# MEZ_ALL_IND.net
KiCad netlist of a schematic drawn in Altium Designer
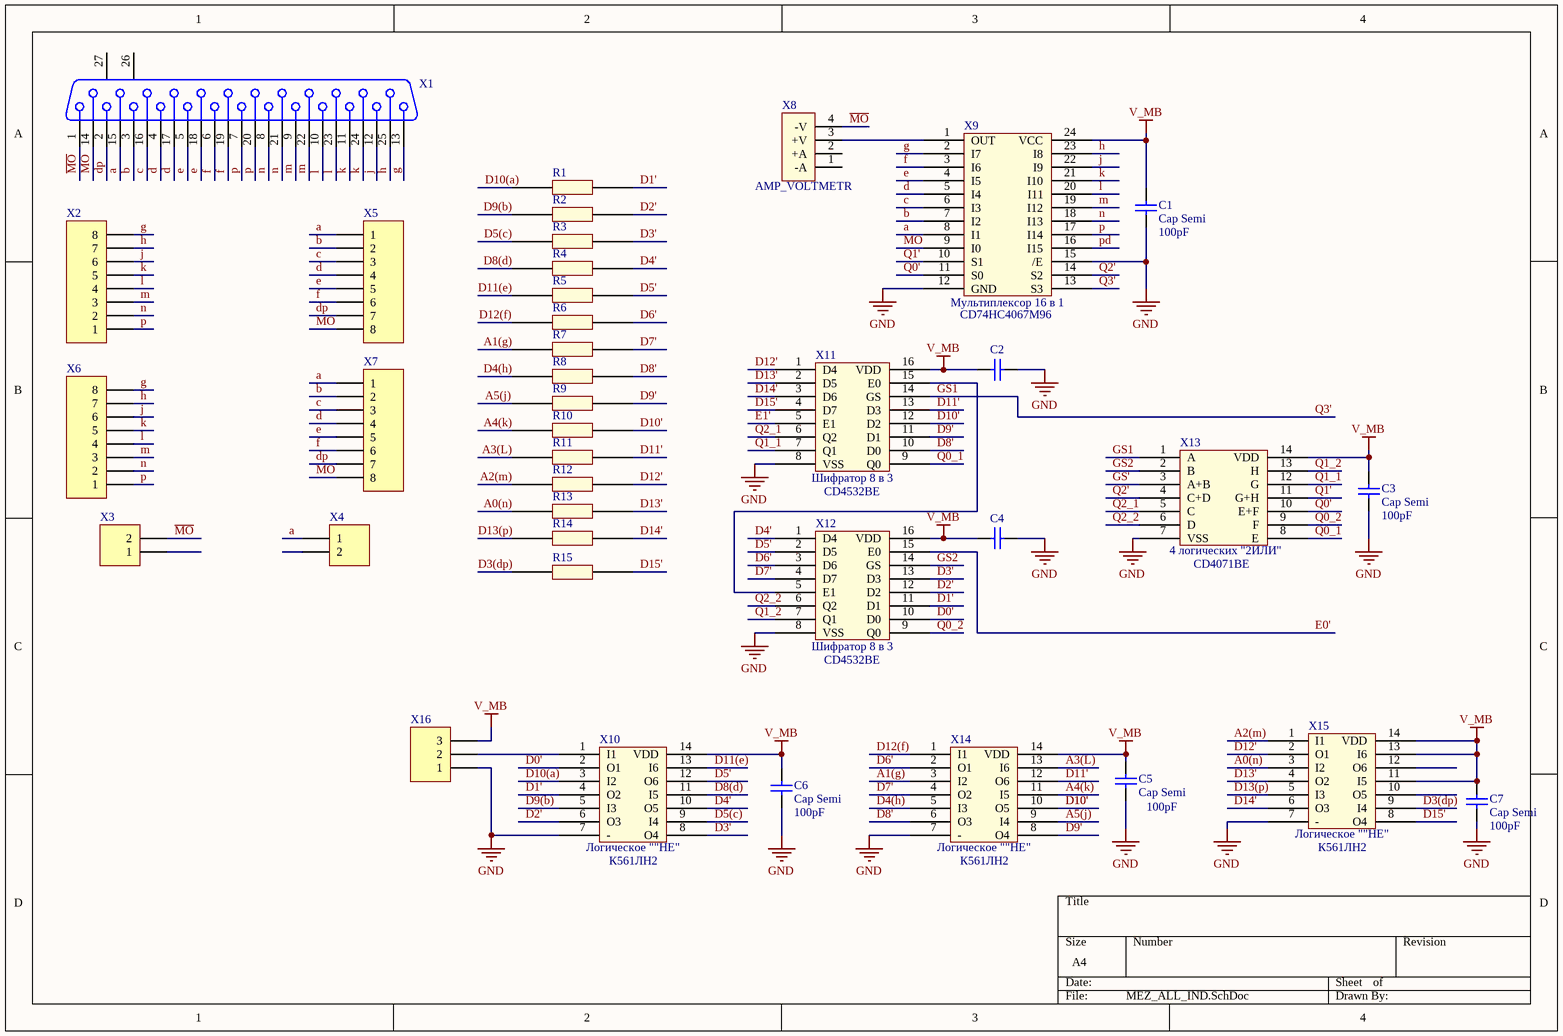
[diagram p0: MEZ_ALL_IND.SchDoc]

(export (version "E")
  (design (tool "Eeschema 10.0.6"))
  (components
    (comp (ref "C1")
      (value "Cap Semi")
      (footprint "C1206")
      (description "Capacitor (Semiconductor SIM Model)")
      (fields (field (name "ALTIUM_VALUE") "100pF") (field (name "PUBLISHER") "Altium Limited"))
      (libsource (lib "Miscellaneous Devices") (part "Cap Semi"))
    )
    (comp (ref "C2")
      (value "Cap Semi")
      (footprint "C1206")
      (description "Capacitor (Semiconductor SIM Model)")
      (fields (field (name "PUBLISHER") "Altium Limited"))
      (libsource (lib "Miscellaneous Devices") (part "Cap Semi"))
    )
    (comp (ref "C3")
      (value "Cap Semi")
      (footprint "C1206")
      (description "Capacitor (Semiconductor SIM Model)")
      (fields (field (name "ALTIUM_VALUE") "100pF") (field (name "PUBLISHER") "Altium Limited"))
      (libsource (lib "Miscellaneous Devices") (part "Cap Semi"))
    )
    (comp (ref "C4")
      (value "Cap Semi")
      (footprint "C1206")
      (description "Capacitor (Semiconductor SIM Model)")
      (fields (field (name "PUBLISHER") "Altium Limited"))
      (libsource (lib "Miscellaneous Devices") (part "Cap Semi"))
    )
    (comp (ref "C5")
      (value "Cap Semi")
      (footprint "C1206")
      (description "Capacitor (Semiconductor SIM Model)")
      (fields (field (name "ALTIUM_VALUE") "100pF") (field (name "PUBLISHER") "Altium Limited"))
      (libsource (lib "Miscellaneous Devices") (part "Cap Semi"))
    )
    (comp (ref "C6")
      (value "Cap Semi")
      (footprint "C1206")
      (description "Capacitor (Semiconductor SIM Model)")
      (fields (field (name "ALTIUM_VALUE") "100pF") (field (name "PUBLISHER") "Altium Limited"))
      (libsource (lib "Miscellaneous Devices") (part "Cap Semi"))
    )
    (comp (ref "C7")
      (value "Cap Semi")
      (footprint "C1206")
      (description "Capacitor (Semiconductor SIM Model)")
      (fields (field (name "ALTIUM_VALUE") "100pF") (field (name "PUBLISHER") "Altium Limited"))
      (libsource (lib "Miscellaneous Devices") (part "Cap Semi"))
    )
    (comp (ref "R1") (value "resistor") (footprint "RES 1608?") (libsource (lib "msp_SchLib") (part "RES")))
    (comp (ref "R2") (value "resistor") (footprint "RES 1608?") (libsource (lib "msp_SchLib") (part "RES")))
    (comp (ref "R3") (value "resistor") (footprint "RES 1608?") (libsource (lib "msp_SchLib") (part "RES")))
    (comp (ref "R4") (value "resistor") (footprint "RES 1608?") (libsource (lib "msp_SchLib") (part "RES")))
    (comp (ref "R5") (value "resistor") (footprint "RES 1608?") (libsource (lib "msp_SchLib") (part "RES")))
    (comp (ref "R6") (value "resistor") (footprint "RES 1608?") (libsource (lib "msp_SchLib") (part "RES")))
    (comp (ref "R7") (value "resistor") (footprint "RES 1608?") (libsource (lib "msp_SchLib") (part "RES")))
    (comp (ref "R8") (value "resistor") (footprint "RES 1608?") (libsource (lib "msp_SchLib") (part "RES")))
    (comp (ref "R9") (value "resistor") (footprint "RES 1608?") (libsource (lib "msp_SchLib") (part "RES")))
    (comp (ref "R10") (value "resistor") (footprint "RES 1608?") (libsource (lib "msp_SchLib") (part "RES")))
    (comp (ref "R11") (value "resistor") (footprint "RES 1608?") (libsource (lib "msp_SchLib") (part "RES")))
    (comp (ref "R12") (value "resistor") (footprint "RES 1608?") (libsource (lib "msp_SchLib") (part "RES")))
    (comp (ref "R13") (value "resistor") (footprint "RES 1608?") (libsource (lib "msp_SchLib") (part "RES")))
    (comp (ref "R14") (value "resistor") (footprint "RES 1608?") (libsource (lib "msp_SchLib") (part "RES")))
    (comp (ref "R15") (value "resistor") (footprint "RES 1608?") (libsource (lib "msp_SchLib") (part "RES")))
    (comp (ref "X1")
      (value "D Connector 25")
      (footprint "DSUB1.385-2H25A")
      (description "Receptacle Assembly, 25 Position, Right Angle")
      (fields (field (name "PUBLISHER") "Altium Limited"))
      (libsource (lib "Miscellaneous Connectors") (part "D Connector 25"))
    )
    (comp (ref "X2")
      (value "Header 8")
      (footprint "HDR1X8")
      (description "Header, 8-Pin")
      (fields (field (name "PUBLISHER") "Altium Limited"))
      (libsource (lib "Miscellaneous Connectors") (part "Header 8"))
    )
    (comp (ref "X3")
      (value "Header 2")
      (footprint "HDR1X2")
      (description "Header, 2-Pin")
      (fields (field (name "PUBLISHER") "Altium Limited"))
      (libsource (lib "Miscellaneous Connectors") (part "Header 2"))
    )
    (comp (ref "X4")
      (value "Header 2")
      (footprint "HDR1X2")
      (description "Header, 2-Pin")
      (fields (field (name "PUBLISHER") "Altium Limited"))
      (libsource (lib "") (part "Header 2_1"))
    )
    (comp (ref "X5")
      (value "Header 8")
      (footprint "HDR1X8")
      (description "Header, 8-Pin")
      (fields (field (name "PUBLISHER") "Altium Limited"))
      (libsource (lib "") (part "Header 8_1"))
    )
    (comp (ref "X6")
      (value "Header 8")
      (footprint "HDR1X8")
      (description "Header, 8-Pin")
      (fields (field (name "PUBLISHER") "Altium Limited"))
      (libsource (lib "Miscellaneous Connectors") (part "Header 8"))
    )
    (comp (ref "X7")
      (value "Header 8")
      (footprint "HDR1X8")
      (description "Header, 8-Pin")
      (fields (field (name "PUBLISHER") "Altium Limited"))
      (libsource (lib "") (part "Header 8_1"))
    )
    (comp (ref "X8")
      (value "AMP_VOLTMETR")
      (footprint "AMP_VOLTMETR")
      (libsource (lib "msp_SchLib") (part "AMP_VOLTMETR"))
    )
    (comp (ref "X9")
      (value "CD74HC4067M96")
      (footprint "SOIC-24")
      (description "16-и канальный аналоговый мультиплексор/ демультиплексор, [SO-24]")
      (libsource (lib "msp_SchLib") (part "CD74HC4067M96"))
    )
    (comp (ref "X10")
      (value "К561ЛН2")
      (description "Шесть логических элементов \"HЕ\" (DIP-14)")
      (libsource (lib "msp_SchLib") (part "К561ЛН2"))
    )
    (comp (ref "X11")
      (value "CD4532BE")
      (description "Шифратор приоритетный 8 - 3 [DIP-16]")
      (libsource (lib "msp_SchLib") (part "CD4532BE"))
    )
    (comp (ref "X12")
      (value "CD4532BE")
      (description "Шифратор приоритетный 8 - 3 [DIP-16]")
      (libsource (lib "msp_SchLib") (part "CD4532BE"))
    )
    (comp (ref "X13")
      (value "CD4071BE")
      (description "Четыре логических элемента \"2ИЛИ\", [DIP-14]")
      (libsource (lib "msp_SchLib") (part "CD4071BE"))
    )
    (comp (ref "X14")
      (value "К561ЛН2")
      (description "Шесть логических элементов \"HЕ\" (DIP-14)")
      (libsource (lib "msp_SchLib") (part "К561ЛН2"))
    )
    (comp (ref "X15")
      (value "К561ЛН2")
      (description "Шесть логических элементов \"HЕ\" (DIP-14)")
      (libsource (lib "msp_SchLib") (part "К561ЛН2"))
    )
    (comp (ref "X16")
      (value "Header 3")
      (footprint "HDR1X3")
      (description "Header, 3-Pin")
      (fields (field (name "PUBLISHER") "Altium Limited"))
      (libsource (lib "Miscellaneous Connectors") (part "Header 3"))
    )
  )
  (nets
    (net (code "1") (name "/A0(n)") (class "Default")
      (node (ref "R13") (pin "1") (pinfunction "1_1") (pintype "passive"))
      (node (ref "X15") (pin "3") (pinfunction "I2_3") (pintype "passive"))
    )
    (net (code "2") (name "/A1(g)") (class "Default")
      (node (ref "R7") (pin "1") (pinfunction "1_1") (pintype "passive"))
      (node (ref "X14") (pin "3") (pinfunction "I2_3") (pintype "passive"))
    )
    (net (code "3") (name "/A2(m)") (class "Default")
      (node (ref "R12") (pin "1") (pinfunction "1_1") (pintype "passive"))
      (node (ref "X15") (pin "1") (pinfunction "I1_1") (pintype "passive"))
    )
    (net (code "4") (name "/A3(L)") (class "Default")
      (node (ref "R11") (pin "1") (pinfunction "1_1") (pintype "passive"))
      (node (ref "X14") (pin "13") (pinfunction "I6_13") (pintype "passive"))
    )
    (net (code "5") (name "/A4(k)") (class "Default")
      (node (ref "R10") (pin "1") (pinfunction "1_1") (pintype "passive"))
      (node (ref "X14") (pin "11") (pinfunction "I5_11") (pintype "passive"))
    )
    (net (code "6") (name "/A5(j)") (class "Default")
      (node (ref "R9") (pin "1") (pinfunction "1_1") (pintype "passive"))
      (node (ref "X14") (pin "9") (pinfunction "I4_9") (pintype "passive"))
    )
    (net (code "7") (name "/D0'") (class "Default")
      (node (ref "X10") (pin "2") (pinfunction "O1_2") (pintype "passive"))
      (node (ref "X12") (pin "10") (pinfunction "D0_10") (pintype "passive"))
    )
    (net (code "8") (name "/D1'") (class "Default")
      (node (ref "R1") (pin "2") (pinfunction "2_2") (pintype "passive"))
      (node (ref "X10") (pin "4") (pinfunction "O2_4") (pintype "passive"))
      (node (ref "X12") (pin "11") (pinfunction "D1_11") (pintype "passive"))
    )
    (net (code "9") (name "/D2'") (class "Default")
      (node (ref "R2") (pin "2") (pinfunction "2_2") (pintype "passive"))
      (node (ref "X10") (pin "6") (pinfunction "O3_6") (pintype "passive"))
      (node (ref "X12") (pin "12") (pinfunction "D2_12") (pintype "passive"))
    )
    (net (code "10") (name "/D3'") (class "Default")
      (node (ref "R3") (pin "2") (pinfunction "2_2") (pintype "passive"))
      (node (ref "X10") (pin "8") (pinfunction "O4_8") (pintype "passive"))
      (node (ref "X12") (pin "13") (pinfunction "D3_13") (pintype "passive"))
    )
    (net (code "11") (name "/D3(dp)") (class "Default")
      (node (ref "R15") (pin "1") (pinfunction "1_1") (pintype "passive"))
      (node (ref "X15") (pin "9") (pinfunction "I4_9") (pintype "passive"))
    )
    (net (code "12") (name "/D4'") (class "Default")
      (node (ref "R4") (pin "2") (pinfunction "2_2") (pintype "passive"))
      (node (ref "X10") (pin "10") (pinfunction "O5_10") (pintype "passive"))
      (node (ref "X12") (pin "1") (pinfunction "D4_1") (pintype "passive"))
    )
    (net (code "13") (name "/D4(h)") (class "Default")
      (node (ref "R8") (pin "1") (pinfunction "1_1") (pintype "passive"))
      (node (ref "X14") (pin "5") (pinfunction "I3_5") (pintype "passive"))
    )
    (net (code "14") (name "/D5'") (class "Default")
      (node (ref "R5") (pin "2") (pinfunction "2_2") (pintype "passive"))
      (node (ref "X10") (pin "12") (pinfunction "O6_12") (pintype "passive"))
      (node (ref "X12") (pin "2") (pinfunction "D5_2") (pintype "passive"))
    )
    (net (code "15") (name "/D5(c)") (class "Default")
      (node (ref "R3") (pin "1") (pinfunction "1_1") (pintype "passive"))
      (node (ref "X10") (pin "9") (pinfunction "I4_9") (pintype "passive"))
    )
    (net (code "16") (name "/D6'") (class "Default")
      (node (ref "R6") (pin "2") (pinfunction "2_2") (pintype "passive"))
      (node (ref "X12") (pin "3") (pinfunction "D6_3") (pintype "passive"))
      (node (ref "X14") (pin "2") (pinfunction "O1_2") (pintype "passive"))
    )
    (net (code "17") (name "/D7'") (class "Default")
      (node (ref "R7") (pin "2") (pinfunction "2_2") (pintype "passive"))
      (node (ref "X12") (pin "4") (pinfunction "D7_4") (pintype "passive"))
      (node (ref "X14") (pin "4") (pinfunction "O2_4") (pintype "passive"))
    )
    (net (code "18") (name "/D8'") (class "Default")
      (node (ref "R8") (pin "2") (pinfunction "2_2") (pintype "passive"))
      (node (ref "X11") (pin "10") (pinfunction "D0_10") (pintype "passive"))
      (node (ref "X14") (pin "6") (pinfunction "O3_6") (pintype "passive"))
    )
    (net (code "19") (name "/D8(d)") (class "Default")
      (node (ref "R4") (pin "1") (pinfunction "1_1") (pintype "passive"))
      (node (ref "X10") (pin "11") (pinfunction "I5_11") (pintype "passive"))
    )
    (net (code "20") (name "/D9'") (class "Default")
      (node (ref "R9") (pin "2") (pinfunction "2_2") (pintype "passive"))
      (node (ref "X11") (pin "11") (pinfunction "D1_11") (pintype "passive"))
      (node (ref "X14") (pin "8") (pinfunction "O4_8") (pintype "passive"))
    )
    (net (code "21") (name "/D9(b)") (class "Default")
      (node (ref "R2") (pin "1") (pinfunction "1_1") (pintype "passive"))
      (node (ref "X10") (pin "5") (pinfunction "I3_5") (pintype "passive"))
    )
    (net (code "22") (name "/D10'") (class "Default")
      (node (ref "R10") (pin "2") (pinfunction "2_2") (pintype "passive"))
      (node (ref "X11") (pin "12") (pinfunction "D2_12") (pintype "passive"))
      (node (ref "X14") (pin "10") (pinfunction "O5_10") (pintype "passive"))
    )
    (net (code "23") (name "/D10(a)") (class "Default")
      (node (ref "R1") (pin "1") (pinfunction "1_1") (pintype "passive"))
      (node (ref "X10") (pin "3") (pinfunction "I2_3") (pintype "passive"))
    )
    (net (code "24") (name "/D11'") (class "Default")
      (node (ref "R11") (pin "2") (pinfunction "2_2") (pintype "passive"))
      (node (ref "X11") (pin "13") (pinfunction "D3_13") (pintype "passive"))
      (node (ref "X14") (pin "12") (pinfunction "O6_12") (pintype "passive"))
    )
    (net (code "25") (name "/D11(e)") (class "Default")
      (node (ref "R5") (pin "1") (pinfunction "1_1") (pintype "passive"))
      (node (ref "X10") (pin "13") (pinfunction "I6_13") (pintype "passive"))
    )
    (net (code "26") (name "/D12'") (class "Default")
      (node (ref "R12") (pin "2") (pinfunction "2_2") (pintype "passive"))
      (node (ref "X11") (pin "1") (pinfunction "D4_1") (pintype "passive"))
      (node (ref "X15") (pin "2") (pinfunction "O1_2") (pintype "passive"))
    )
    (net (code "27") (name "/D12(f)") (class "Default")
      (node (ref "R6") (pin "1") (pinfunction "1_1") (pintype "passive"))
      (node (ref "X14") (pin "1") (pinfunction "I1_1") (pintype "passive"))
    )
    (net (code "28") (name "/D13'") (class "Default")
      (node (ref "R13") (pin "2") (pinfunction "2_2") (pintype "passive"))
      (node (ref "X11") (pin "2") (pinfunction "D5_2") (pintype "passive"))
      (node (ref "X15") (pin "4") (pinfunction "O2_4") (pintype "passive"))
    )
    (net (code "29") (name "/D13(p)") (class "Default")
      (node (ref "R14") (pin "1") (pinfunction "1_1") (pintype "passive"))
      (node (ref "X15") (pin "5") (pinfunction "I3_5") (pintype "passive"))
    )
    (net (code "30") (name "/D14'") (class "Default")
      (node (ref "R14") (pin "2") (pinfunction "2_2") (pintype "passive"))
      (node (ref "X11") (pin "3") (pinfunction "D6_3") (pintype "passive"))
      (node (ref "X15") (pin "6") (pinfunction "O3_6") (pintype "passive"))
    )
    (net (code "31") (name "/D15'") (class "Default")
      (node (ref "R15") (pin "2") (pinfunction "2_2") (pintype "passive"))
      (node (ref "X11") (pin "4") (pinfunction "D7_4") (pintype "passive"))
      (node (ref "X15") (pin "8") (pinfunction "O4_8") (pintype "passive"))
    )
    (net (code "32") (name "/E0'") (class "Default")
      (node (ref "X12") (pin "15") (pinfunction "E0_15") (pintype "passive"))
    )
    (net (code "33") (name "/E1'") (class "Default")
      (node (ref "X11") (pin "5") (pinfunction "E1_5") (pintype "passive"))
    )
    (net (code "34") (name "/GS'") (class "Default")
      (node (ref "X13") (pin "3") (pinfunction "A+B_3") (pintype "passive"))
    )
    (net (code "35") (name "/GS1") (class "Default")
      (node (ref "X11") (pin "14") (pinfunction "GS_14") (pintype "passive"))
      (node (ref "X13") (pin "1") (pinfunction "A_1") (pintype "passive"))
      (node (ref "X9") (pin "13") (pinfunction "S3_13") (pintype "passive"))
    )
    (net (code "36") (name "/GS2") (class "Default")
      (node (ref "X12") (pin "14") (pinfunction "GS_14") (pintype "passive"))
      (node (ref "X13") (pin "2") (pinfunction "B_2") (pintype "passive"))
    )
    (net (code "37") (name "/Q0'") (class "Default")
      (node (ref "X13") (pin "10") (pinfunction "E+F_10") (pintype "passive"))
      (node (ref "X9") (pin "11") (pinfunction "S0_11") (pintype "passive"))
    )
    (net (code "38") (name "/Q0_1") (class "Default")
      (node (ref "X11") (pin "9") (pinfunction "Q0_9") (pintype "passive"))
      (node (ref "X13") (pin "8") (pinfunction "E_8") (pintype "passive"))
    )
    (net (code "39") (name "/Q0_2") (class "Default")
      (node (ref "X12") (pin "9") (pinfunction "Q0_9") (pintype "passive"))
      (node (ref "X13") (pin "9") (pinfunction "F_9") (pintype "passive"))
    )
    (net (code "40") (name "/Q1'") (class "Default")
      (node (ref "X13") (pin "11") (pinfunction "G+H_11") (pintype "passive"))
      (node (ref "X9") (pin "10") (pinfunction "S1_10") (pintype "passive"))
    )
    (net (code "41") (name "/Q1_1") (class "Default")
      (node (ref "X11") (pin "7") (pinfunction "Q1_7") (pintype "passive"))
      (node (ref "X13") (pin "12") (pinfunction "G_12") (pintype "passive"))
    )
    (net (code "42") (name "/Q1_2") (class "Default")
      (node (ref "X12") (pin "7") (pinfunction "Q1_7") (pintype "passive"))
      (node (ref "X13") (pin "13") (pinfunction "H_13") (pintype "passive"))
    )
    (net (code "43") (name "/Q2'") (class "Default")
      (node (ref "X13") (pin "4") (pinfunction "C+D_4") (pintype "passive"))
      (node (ref "X9") (pin "14") (pinfunction "S2_14") (pintype "passive"))
    )
    (net (code "44") (name "/Q2_1") (class "Default")
      (node (ref "X11") (pin "6") (pinfunction "Q2_6") (pintype "passive"))
      (node (ref "X13") (pin "5") (pinfunction "C_5") (pintype "passive"))
    )
    (net (code "45") (name "/Q2_2") (class "Default")
      (node (ref "X12") (pin "6") (pinfunction "Q2_6") (pintype "passive"))
      (node (ref "X13") (pin "6") (pinfunction "D_6") (pintype "passive"))
    )
    (net (code "46") (name "/a") (class "Default")
      (node (ref "X1") (pin "15") (pinfunction "15_15") (pintype "passive"))
      (node (ref "X4") (pin "1") (pinfunction "1_1") (pintype "passive"))
      (node (ref "X5") (pin "1") (pinfunction "1_1") (pintype "passive"))
      (node (ref "X7") (pin "1") (pinfunction "1_1") (pintype "passive"))
      (node (ref "X9") (pin "8") (pinfunction "I1_8") (pintype "passive"))
    )
    (net (code "47") (name "/b") (class "Default")
      (node (ref "X1") (pin "3") (pinfunction "3_3") (pintype "passive"))
      (node (ref "X5") (pin "2") (pinfunction "2_2") (pintype "passive"))
      (node (ref "X7") (pin "2") (pinfunction "2_2") (pintype "passive"))
      (node (ref "X9") (pin "7") (pinfunction "I2_7") (pintype "passive"))
    )
    (net (code "48") (name "/c") (class "Default")
      (node (ref "X1") (pin "16") (pinfunction "16_16") (pintype "passive"))
      (node (ref "X5") (pin "3") (pinfunction "3_3") (pintype "passive"))
      (node (ref "X7") (pin "3") (pinfunction "3_3") (pintype "passive"))
      (node (ref "X9") (pin "6") (pinfunction "I3_6") (pintype "passive"))
    )
    (net (code "49") (name "/d") (class "Default")
      (node (ref "X1") (pin "17") (pinfunction "17_17") (pintype "passive"))
      (node (ref "X1") (pin "4") (pinfunction "4_4") (pintype "passive"))
      (node (ref "X5") (pin "4") (pinfunction "4_4") (pintype "passive"))
      (node (ref "X7") (pin "4") (pinfunction "4_4") (pintype "passive"))
      (node (ref "X9") (pin "5") (pinfunction "I4_5") (pintype "passive"))
    )
    (net (code "50") (name "/dp") (class "Default")
      (node (ref "X1") (pin "2") (pinfunction "2_2") (pintype "passive"))
      (node (ref "X5") (pin "7") (pinfunction "7_7") (pintype "passive"))
      (node (ref "X7") (pin "7") (pinfunction "7_7") (pintype "passive"))
    )
    (net (code "51") (name "/e") (class "Default")
      (node (ref "X1") (pin "18") (pinfunction "18_18") (pintype "passive"))
      (node (ref "X1") (pin "5") (pinfunction "5_5") (pintype "passive"))
      (node (ref "X5") (pin "5") (pinfunction "5_5") (pintype "passive"))
      (node (ref "X7") (pin "5") (pinfunction "5_5") (pintype "passive"))
      (node (ref "X9") (pin "4") (pinfunction "I5_4") (pintype "passive"))
    )
    (net (code "52") (name "/f") (class "Default")
      (node (ref "X1") (pin "19") (pinfunction "19_19") (pintype "passive"))
      (node (ref "X1") (pin "6") (pinfunction "6_6") (pintype "passive"))
      (node (ref "X5") (pin "6") (pinfunction "6_6") (pintype "passive"))
      (node (ref "X7") (pin "6") (pinfunction "6_6") (pintype "passive"))
      (node (ref "X9") (pin "3") (pinfunction "I6_3") (pintype "passive"))
    )
    (net (code "53") (name "/g") (class "Default")
      (node (ref "X1") (pin "13") (pinfunction "13_13") (pintype "passive"))
      (node (ref "X2") (pin "8") (pinfunction "8_8") (pintype "passive"))
      (node (ref "X6") (pin "8") (pinfunction "8_8") (pintype "passive"))
      (node (ref "X9") (pin "2") (pinfunction "I7_2") (pintype "passive"))
    )
    (net (code "54") (name "/h") (class "Default")
      (node (ref "X1") (pin "25") (pinfunction "25_25") (pintype "passive"))
      (node (ref "X2") (pin "7") (pinfunction "7_7") (pintype "passive"))
      (node (ref "X6") (pin "7") (pinfunction "7_7") (pintype "passive"))
      (node (ref "X9") (pin "23") (pinfunction "I8_23") (pintype "passive"))
    )
    (net (code "55") (name "/j") (class "Default")
      (node (ref "X1") (pin "12") (pinfunction "12_12") (pintype "passive"))
      (node (ref "X2") (pin "6") (pinfunction "6_6") (pintype "passive"))
      (node (ref "X6") (pin "6") (pinfunction "6_6") (pintype "passive"))
      (node (ref "X9") (pin "22") (pinfunction "I9_22") (pintype "passive"))
    )
    (net (code "56") (name "/k") (class "Default")
      (node (ref "X1") (pin "11") (pinfunction "11_11") (pintype "passive"))
      (node (ref "X1") (pin "24") (pinfunction "24_24") (pintype "passive"))
      (node (ref "X2") (pin "5") (pinfunction "5_5") (pintype "passive"))
      (node (ref "X6") (pin "5") (pinfunction "5_5") (pintype "passive"))
      (node (ref "X9") (pin "21") (pinfunction "I10_21") (pintype "passive"))
    )
    (net (code "57") (name "/l") (class "Default")
      (node (ref "X1") (pin "10") (pinfunction "10_10") (pintype "passive"))
      (node (ref "X1") (pin "23") (pinfunction "23_23") (pintype "passive"))
      (node (ref "X2") (pin "4") (pinfunction "4_4") (pintype "passive"))
      (node (ref "X6") (pin "4") (pinfunction "4_4") (pintype "passive"))
      (node (ref "X9") (pin "20") (pinfunction "I11_20") (pintype "passive"))
    )
    (net (code "58") (name "/m") (class "Default")
      (node (ref "X1") (pin "22") (pinfunction "22_22") (pintype "passive"))
      (node (ref "X1") (pin "9") (pinfunction "9_9") (pintype "passive"))
      (node (ref "X2") (pin "3") (pinfunction "3_3") (pintype "passive"))
      (node (ref "X6") (pin "3") (pinfunction "3_3") (pintype "passive"))
      (node (ref "X9") (pin "19") (pinfunction "I12_19") (pintype "passive"))
    )
    (net (code "59") (name "/n") (class "Default")
      (node (ref "X1") (pin "21") (pinfunction "21_21") (pintype "passive"))
      (node (ref "X1") (pin "8") (pinfunction "8_8") (pintype "passive"))
      (node (ref "X2") (pin "2") (pinfunction "2_2") (pintype "passive"))
      (node (ref "X6") (pin "2") (pinfunction "2_2") (pintype "passive"))
      (node (ref "X9") (pin "18") (pinfunction "I13_18") (pintype "passive"))
    )
    (net (code "60") (name "/p") (class "Default")
      (node (ref "X1") (pin "20") (pinfunction "20_20") (pintype "passive"))
      (node (ref "X1") (pin "7") (pinfunction "7_7") (pintype "passive"))
      (node (ref "X2") (pin "1") (pinfunction "1_1") (pintype "passive"))
      (node (ref "X6") (pin "1") (pinfunction "1_1") (pintype "passive"))
      (node (ref "X9") (pin "17") (pinfunction "I14_17") (pintype "passive"))
    )
    (net (code "61") (name "/pd") (class "Default")
      (node (ref "X9") (pin "16") (pinfunction "I15_16") (pintype "passive"))
    )
    (net (code "62") (name "/~{MO}") (class "Default")
      (node (ref "X1") (pin "1") (pinfunction "1_1") (pintype "passive"))
      (node (ref "X1") (pin "14") (pinfunction "14_14") (pintype "passive"))
      (node (ref "X3") (pin "2") (pinfunction "2_2") (pintype "passive"))
      (node (ref "X5") (pin "8") (pinfunction "8_8") (pintype "passive"))
      (node (ref "X7") (pin "8") (pinfunction "8_8") (pintype "passive"))
      (node (ref "X8") (pin "4") (pinfunction "-V_4") (pintype "passive"))
      (node (ref "X9") (pin "9") (pinfunction "I0_9") (pintype "passive"))
    )
    (net (code "63") (name "GND") (class "Default")
      (node (ref "C1") (pin "1") (pinfunction "1_1") (pintype "passive"))
      (node (ref "C2") (pin "1") (pinfunction "1_1") (pintype "passive"))
      (node (ref "C3") (pin "1") (pinfunction "1_1") (pintype "passive"))
      (node (ref "C4") (pin "1") (pinfunction "1_1") (pintype "passive"))
      (node (ref "C5") (pin "1") (pinfunction "1_1") (pintype "passive"))
      (node (ref "C6") (pin "1") (pinfunction "1_1") (pintype "passive"))
      (node (ref "C7") (pin "1") (pinfunction "1_1") (pintype "passive"))
      (node (ref "X10") (pin "7") (pinfunction "-_7") (pintype "passive"))
      (node (ref "X11") (pin "8") (pinfunction "VSS_8") (pintype "passive"))
      (node (ref "X12") (pin "8") (pinfunction "VSS_8") (pintype "passive"))
      (node (ref "X13") (pin "7") (pinfunction "VSS_7") (pintype "passive"))
      (node (ref "X14") (pin "7") (pinfunction "-_7") (pintype "passive"))
      (node (ref "X15") (pin "7") (pinfunction "-_7") (pintype "passive"))
      (node (ref "X16") (pin "1") (pinfunction "1_1") (pintype "passive"))
      (node (ref "X9") (pin "12") (pinfunction "GND_12") (pintype "passive"))
      (node (ref "X9") (pin "15") (pinfunction "/E_15") (pintype "passive"))
    )
    (net (code "64") (name "Net-(X8-+V)") (class "Default")
      (node (ref "X8") (pin "3") (pinfunction "+V_3") (pintype "passive"))
      (node (ref "X9") (pin "1") (pinfunction "OUT_1") (pintype "passive"))
    )
    (net (code "65") (name "Net-(X10-I1)") (class "Default")
      (node (ref "X10") (pin "1") (pinfunction "I1_1") (pintype "passive"))
      (node (ref "X16") (pin "2") (pinfunction "2_2") (pintype "passive"))
    )
    (net (code "66") (name "Net-(X11-E0)") (class "Default")
      (node (ref "X11") (pin "15") (pinfunction "E0_15") (pintype "passive"))
      (node (ref "X12") (pin "5") (pinfunction "E1_5") (pintype "passive"))
    )
    (net (code "67") (name "V_MB") (class "Default")
      (node (ref "C1") (pin "2") (pinfunction "2_2") (pintype "passive"))
      (node (ref "C2") (pin "2") (pinfunction "2_2") (pintype "passive"))
      (node (ref "C3") (pin "2") (pinfunction "2_2") (pintype "passive"))
      (node (ref "C4") (pin "2") (pinfunction "2_2") (pintype "passive"))
      (node (ref "C5") (pin "2") (pinfunction "2_2") (pintype "passive"))
      (node (ref "C6") (pin "2") (pinfunction "2_2") (pintype "passive"))
      (node (ref "C7") (pin "2") (pinfunction "2_2") (pintype "passive"))
      (node (ref "X10") (pin "14") (pinfunction "VDD_14") (pintype "passive"))
      (node (ref "X11") (pin "16") (pinfunction "VDD_16") (pintype "passive"))
      (node (ref "X12") (pin "16") (pinfunction "VDD_16") (pintype "passive"))
      (node (ref "X13") (pin "14") (pinfunction "VDD_14") (pintype "passive"))
      (node (ref "X14") (pin "14") (pinfunction "VDD_14") (pintype "passive"))
      (node (ref "X15") (pin "11") (pinfunction "I5_11") (pintype "passive"))
      (node (ref "X15") (pin "13") (pinfunction "I6_13") (pintype "passive"))
      (node (ref "X15") (pin "14") (pinfunction "VDD_14") (pintype "passive"))
      (node (ref "X16") (pin "3") (pinfunction "3_3") (pintype "passive"))
      (node (ref "X9") (pin "24") (pinfunction "VCC_24") (pintype "passive"))
    )
    (net (code "68") (name "unconnected-(X1-MH1-Pad26)") (class "Default")
      (node (ref "X1") (pin "26") (pinfunction "MH1_26") (pintype "passive"))
    )
    (net (code "69") (name "unconnected-(X1-MH2-Pad27)") (class "Default")
      (node (ref "X1") (pin "27") (pinfunction "MH2_27") (pintype "passive"))
    )
    (net (code "70") (name "unconnected-(X3-Pad1)") (class "Default")
      (node (ref "X3") (pin "1") (pinfunction "1_1") (pintype "passive"))
    )
    (net (code "71") (name "unconnected-(X4-Pad2)") (class "Default")
      (node (ref "X4") (pin "2") (pinfunction "2_2") (pintype "passive"))
    )
    (net (code "72") (name "unconnected-(X8-+A-Pad2)") (class "Default")
      (node (ref "X8") (pin "2") (pinfunction "+A_2") (pintype "passive"))
    )
    (net (code "73") (name "unconnected-(X8--A-Pad1)") (class "Default")
      (node (ref "X8") (pin "1") (pinfunction "-A_1") (pintype "passive"))
    )
    (net (code "74") (name "unconnected-(X15-O5-Pad10)") (class "Default")
      (node (ref "X15") (pin "10") (pinfunction "O5_10") (pintype "passive"))
    )
    (net (code "75") (name "unconnected-(X15-O6-Pad12)") (class "Default")
      (node (ref "X15") (pin "12") (pinfunction "O6_12") (pintype "passive"))
    )
  )
)
